# POWER_VOLTAGE.net
KiCad netlist of a schematic drawn in Altium Designer
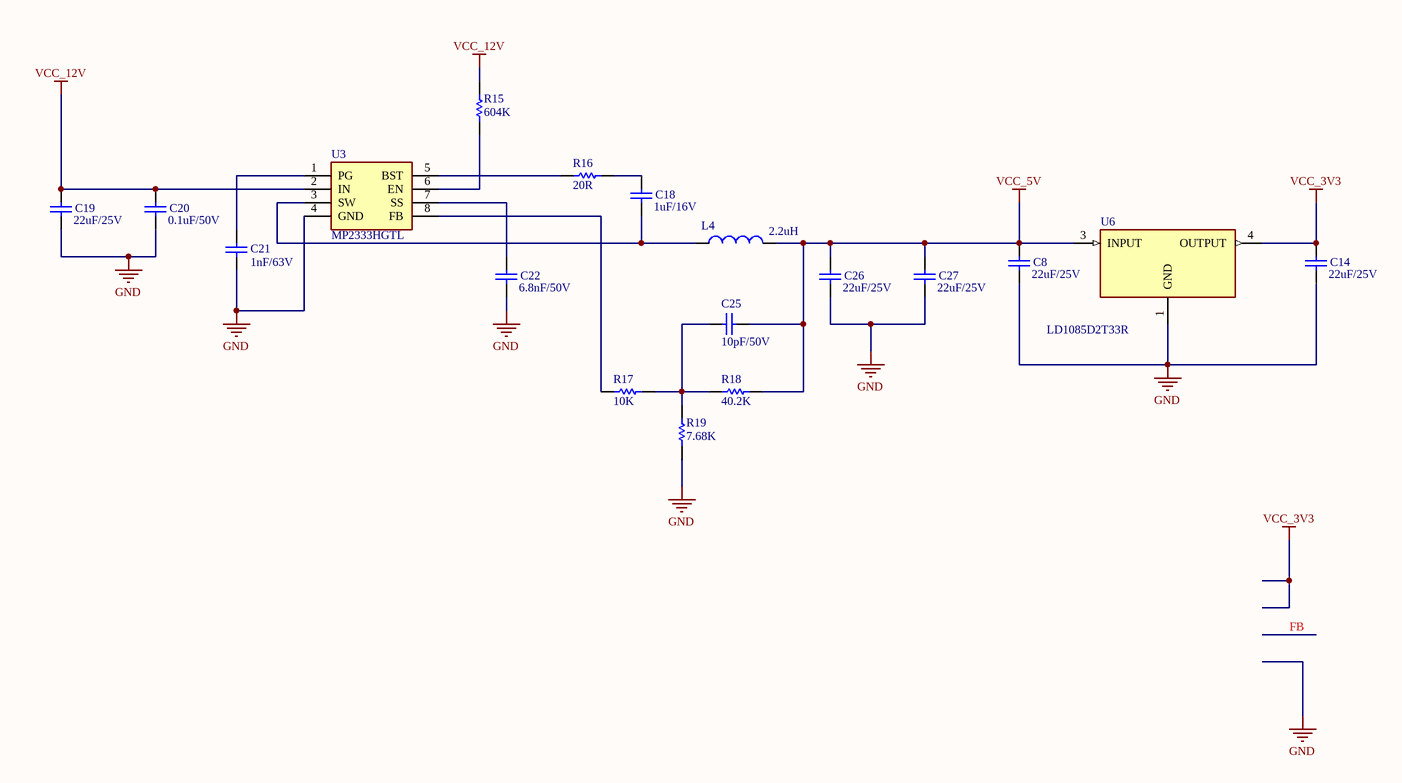
[diagram p0: POWER_VOLTAGE.SchDoc]

(export (version "E")
  (design (tool "Eeschema 10.0.6"))
  (components
    (comp (ref "C8")
      (value "22uF/25V")
      (footprint "1210C")
      (description "Multilayer Ceramic Capacitors MLCC - SMD/SMT 1210 25VDC 22uF 20% X7R AEC-Q200")
      (fields (field (name "MFR") "Taiyo Yuden") (field (name "MFR PART NO") "TMK325B7226MMHP"))
      (libsource (lib "Miscellaneous Devices") (part "Cap"))
    )
    (comp (ref "C14")
      (value "22uF/25V")
      (footprint "1210C")
      (description "Multilayer Ceramic Capacitors MLCC - SMD/SMT 1210 25VDC 22uF 20% X7R AEC-Q200")
      (fields (field (name "MFR") "Taiyo Yuden") (field (name "MFR PART NO") "TMK325B7226MMHP"))
      (libsource (lib "Miscellaneous Devices") (part "Cap"))
    )
    (comp (ref "C18")
      (value "1uF/16V")
      (footprint "0603C")
      (description "Multilayer Ceramic Capacitors MLCC - SMD/SMT 16volts 1uF X7R 10%")
      (fields (field (name "MFR") "KEMET") (field (name "MFR PART NO") "C0603C105K4RAC7411"))
      (libsource (lib "Miscellaneous Devices") (part "Cap"))
    )
    (comp (ref "C19")
      (value "22uF/25V")
      (footprint "1210C")
      (description "Multilayer Ceramic Capacitors MLCC - SMD/SMT 1210 25VDC 22uF 20% X7R AEC-Q200")
      (fields (field (name "MFR") "Taiyo Yuden") (field (name "MFR PART NO") "TMK325B7226MMHP"))
      (libsource (lib "Miscellaneous Devices") (part "Cap"))
    )
    (comp (ref "C20")
      (value "0.1uF/50V")
      (footprint "0603C")
      (description "Multilayer Ceramic Capacitors MLCC - SMD/SMT 50V 0.1uF 0603 X7R 20%")
      (fields (field (name "MFR") "KEMET") (field (name "MFR PART NO") "C0603C104M5RACTU"))
      (libsource (lib "Miscellaneous Devices") (part "Cap"))
    )
    (comp (ref "C21")
      (value "1nF/63V")
      (footprint "0603C")
      (description "Multilayer Ceramic Capacitors MLCC - SMD/SMT 63V 1000pF 0603 X7R 10% AEC-Q200")
      (fields (field (name "MFR") "KEMET") (field (name "MFR PART NO") "80-C0603C102KMREAUTO"))
      (libsource (lib "Miscellaneous Devices") (part "Cap"))
    )
    (comp (ref "C22")
      (value "6.8nF/50V")
      (footprint "0603C")
      (description "Multilayer Ceramic Capacitors MLCC - SMD/SMT 0603 50VDC 6.8nF 5% C0G AEC-Q200")
      (fields (field (name "MFR") "TDK") (field (name "MFR PART NO") "CGA3E2C0G1H682J080AE"))
      (libsource (lib "Miscellaneous Devices") (part "Cap"))
    )
    (comp (ref "C25")
      (value "10pF/50V")
      (footprint "0603C")
      (description "Multilayer Ceramic Capacitors MLCC - SMD/SMT 50V 10pF 0603 C0G 5% AEC-Q200")
      (fields (field (name "MFR") "KEMET") (field (name "MFR PART NO") "C0603C100J5GACAUTO"))
      (libsource (lib "Miscellaneous Devices") (part "Cap"))
    )
    (comp (ref "C26")
      (value "22uF/25V")
      (footprint "1210C")
      (description "Multilayer Ceramic Capacitors MLCC - SMD/SMT 1210 25VDC 22uF 20% X7R AEC-Q200")
      (fields (field (name "MFR") "Taiyo Yuden") (field (name "MFR PART NO") "TMK325B7226MMHP"))
      (libsource (lib "Miscellaneous Devices") (part "Cap"))
    )
    (comp (ref "C27")
      (value "22uF/25V")
      (footprint "1210C")
      (description "Multilayer Ceramic Capacitors MLCC - SMD/SMT 1210 25VDC 22uF 20% X7R AEC-Q200")
      (fields (field (name "MFR") "Taiyo Yuden") (field (name "MFR PART NO") "TMK325B7226MMHP"))
      (libsource (lib "Miscellaneous Devices") (part "Cap"))
    )
    (comp (ref "L4")
      (value "2.2uH")
      (footprint "IHLP1616BZER2R2M5A")
      (description "Fixed Inductors 2.2uH 20% High Temp AEC-Q200")
      (fields (field (name "MFR") "Vishay / Dale") (field (name "MFR PART NO") "IHLP1616BZER2R2M5A"))
      (libsource (lib "de20") (part "INDUCTOR"))
    )
    (comp (ref "R15")
      (value "604K")
      (footprint "0603R")
      (description "Thick Film Resistors - SMD 0603 1% 604Kohm Anti-Sulfur AEC-Q200")
      (fields (field (name "MFR") "Panasonic") (field (name "MFR PART NO") "ERJ-U03F6043V"))
      (libsource (lib "Miscellaneous Devices") (part "Res1"))
    )
    (comp (ref "R16")
      (value "20R")
      (footprint "0603R")
      (description "Thick Film Resistors - SMD 0603 0.25W 1% 20ohm AEC-Q200")
      (fields (field (name "MFR") "Panasonic") (field (name "MFR PART NO") "ERJ-UP3F20R0V"))
      (libsource (lib "Miscellaneous Devices") (part "Res1"))
    )
    (comp (ref "R17")
      (value "10K")
      (footprint "0603R")
      (description "Thick Film Resistors - SMD 0603 10Kohms 1% Anti-Sulfur AEC-Q200")
      (fields (field (name "MFR") "ROHM Semiconductor") (field (name "MFR PART NO") "SFR03EZPF1002"))
      (libsource (lib "Miscellaneous Devices") (part "Res1"))
    )
    (comp (ref "R18")
      (value "40.2K")
      (footprint "0603R")
      (description "Thick Film Resistors - SMD 0603 Anti-Surge Res. 0.1%, 40.2Koh")
      (fields (field (name "MFR") "Panasonic") (field (name "MFR PART NO") "ERJ-PB3B4022V"))
      (libsource (lib "Miscellaneous Devices") (part "Res1"))
    )
    (comp (ref "R19")
      (value "7.68K")
      (footprint "0603R")
      (description "Thick Film Resistors - SMD 0603 Anti-Surge Res. 0.1%, 7.68Koh")
      (fields (field (name "MFR") "Panasonic") (field (name "MFR PART NO") "ERJ-PB3B7681V"))
      (libsource (lib "Miscellaneous Devices") (part "Res1"))
    )
    (comp (ref "U3")
      (value "MP2333HGTL")
      (footprint "MP2333HGTL-P")
      (description "Switching Voltage Regulators High-Efficiency, 3A, 18V, 1200kHz, Synchronous, Step-Down Converter")
      (fields
        (field (name "MFR") "Monolithic Power Systems (MPS)")
        (field (name "MFR PART NO") "MP2333HGTL-P")
      )
      (libsource (lib "*") (part "MP2333HGTL"))
    )
    (comp (ref "U6")
      (value "LD1085D2T33R")
      (footprint "LD1085D2T33R")
      (description "Integrated Circuit")
      (fields
        (field (name "MFR") "STMicroelectronics")
        (field (name "STOCKIEST PART NO") "511-LD1085D2T33-TR")
      )
      (libsource (lib "*") (part "LD1085D2T33R"))
    )
  )
  (nets
    (net (code "2") (name "GND") (class "Default")
      (node (ref "C14") (pin "1") (pinfunction "1_1") (pintype "passive"))
      (node (ref "C19") (pin "1") (pinfunction "1_1") (pintype "passive"))
      (node (ref "C20") (pin "1") (pinfunction "1_1") (pintype "passive"))
      (node (ref "C21") (pin "1") (pinfunction "1_1") (pintype "passive"))
      (node (ref "C22") (pin "1") (pinfunction "1_1") (pintype "passive"))
      (node (ref "C26") (pin "1") (pinfunction "1_1") (pintype "passive"))
      (node (ref "C27") (pin "1") (pinfunction "1_1") (pintype "passive"))
      (node (ref "C8") (pin "1") (pinfunction "1_1") (pintype "passive"))
      (node (ref "R19") (pin "2") (pinfunction "2_2") (pintype "passive"))
      (node (ref "U3") (pin "4") (pinfunction "GND_4") (pintype "passive"))
      (node (ref "U6") (pin "1") (pinfunction "GND_1") (pintype "power_in"))
    )
    (net (code "3") (name "Net-(C18-Pad2)") (class "Default")
      (node (ref "C18") (pin "2") (pinfunction "2_2") (pintype "passive"))
      (node (ref "R16") (pin "2") (pinfunction "2_2") (pintype "passive"))
    )
    (net (code "4") (name "Net-(C25-Pad2)") (class "Default")
      (node (ref "C25") (pin "2") (pinfunction "2_2") (pintype "passive"))
      (node (ref "R17") (pin "1") (pinfunction "1_1") (pintype "passive"))
      (node (ref "R18") (pin "1") (pinfunction "1_1") (pintype "passive"))
      (node (ref "R19") (pin "1") (pinfunction "1_1") (pintype "passive"))
    )
    (net (code "5") (name "Net-(U3-BST)") (class "Default")
      (node (ref "R16") (pin "1") (pinfunction "1_1") (pintype "passive"))
      (node (ref "U3") (pin "5") (pinfunction "BST_5") (pintype "passive"))
    )
    (net (code "6") (name "Net-(U3-EN)") (class "Default")
      (node (ref "R15") (pin "1") (pinfunction "1_1") (pintype "passive"))
      (node (ref "U3") (pin "6") (pinfunction "EN_6") (pintype "passive"))
    )
    (net (code "7") (name "Net-(U3-FB)") (class "Default")
      (node (ref "R17") (pin "2") (pinfunction "2_2") (pintype "passive"))
      (node (ref "U3") (pin "8") (pinfunction "FB_8") (pintype "passive"))
    )
    (net (code "8") (name "Net-(U3-PG)") (class "Default")
      (node (ref "C21") (pin "2") (pinfunction "2_2") (pintype "passive"))
      (node (ref "U3") (pin "1") (pinfunction "PG_1") (pintype "passive"))
    )
    (net (code "9") (name "Net-(U3-SS)") (class "Default")
      (node (ref "C22") (pin "2") (pinfunction "2_2") (pintype "passive"))
      (node (ref "U3") (pin "7") (pinfunction "SS_7") (pintype "passive"))
    )
    (net (code "10") (name "Net-(U3-SW)") (class "Default")
      (node (ref "C18") (pin "1") (pinfunction "1_1") (pintype "passive"))
      (node (ref "L4") (pin "1") (pinfunction "1_1") (pintype "passive"))
      (node (ref "U3") (pin "3") (pinfunction "SW_3") (pintype "passive"))
    )
    (net (code "11") (name "VCC_3V3") (class "Default")
      (node (ref "C14") (pin "2") (pinfunction "2_2") (pintype "passive"))
      (node (ref "U6") (pin "4") (pinfunction "OUTPUT_4") (pintype "output"))
    )
    (net (code "12") (name "VCC_5V") (class "Default")
      (node (ref "C25") (pin "1") (pinfunction "1_1") (pintype "passive"))
      (node (ref "C26") (pin "2") (pinfunction "2_2") (pintype "passive"))
      (node (ref "C27") (pin "2") (pinfunction "2_2") (pintype "passive"))
      (node (ref "C8") (pin "2") (pinfunction "2_2") (pintype "passive"))
      (node (ref "L4") (pin "2") (pinfunction "2_2") (pintype "passive"))
      (node (ref "R18") (pin "2") (pinfunction "2_2") (pintype "passive"))
      (node (ref "U6") (pin "3") (pinfunction "INPUT_3") (pintype "input"))
    )
    (net (code "13") (name "VCC_12V") (class "Default")
      (node (ref "C19") (pin "2") (pinfunction "2_2") (pintype "passive"))
      (node (ref "C20") (pin "2") (pinfunction "2_2") (pintype "passive"))
      (node (ref "R15") (pin "2") (pinfunction "2_2") (pintype "passive"))
      (node (ref "U3") (pin "2") (pinfunction "IN_2") (pintype "passive"))
    )
  )
)
